# AFE.net
KiCad netlist of a schematic drawn in Altium Designer
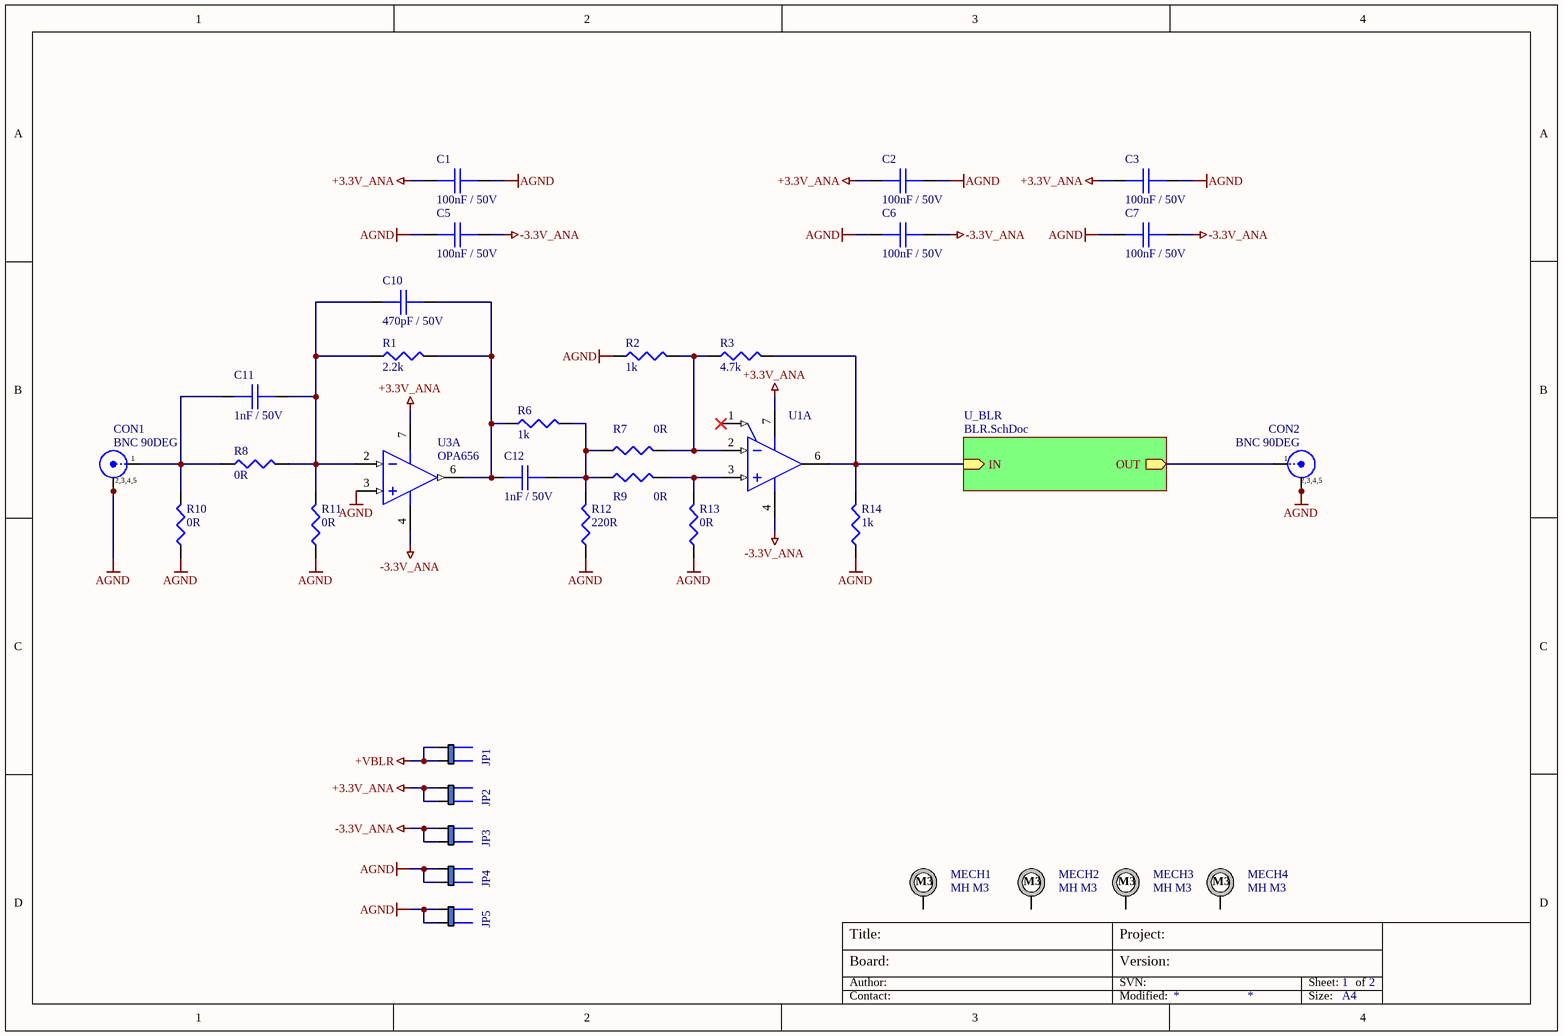
[diagram p0: AFE.SchDoc]

(export (version "E")
  (design (tool "Eeschema 10.0.6"))
  (components
    (comp (ref "C1")
      (value "100nF / 50V")
      (footprint "1206_C")
      (description "100nF 50V X7R")
      (fields (field (name "PART NUMBER") "SMD1206-100nF-50V"))
      (libsource (lib "ALTIUM_DB_LIB") (part "CAP_NONPOL"))
    )
    (comp (ref "C2")
      (value "100nF / 50V")
      (footprint "1206_C")
      (description "100nF 50V X7R")
      (fields (field (name "PART NUMBER") "SMD1206-100nF-50V"))
      (libsource (lib "ALTIUM_DB_LIB") (part "CAP_NONPOL"))
    )
    (comp (ref "C3")
      (value "100nF / 50V")
      (footprint "1206_C")
      (description "100nF 50V X7R")
      (fields (field (name "PART NUMBER") "SMD1206-100nF-50V"))
      (libsource (lib "ALTIUM_DB_LIB") (part "CAP_NONPOL"))
    )
    (comp (ref "C5")
      (value "100nF / 50V")
      (footprint "1206_C")
      (description "100nF 50V X7R")
      (fields (field (name "PART NUMBER") "SMD1206-100nF-50V"))
      (libsource (lib "ALTIUM_DB_LIB") (part "CAP_NONPOL"))
    )
    (comp (ref "C6")
      (value "100nF / 50V")
      (footprint "1206_C")
      (description "100nF 50V X7R")
      (fields (field (name "PART NUMBER") "SMD1206-100nF-50V"))
      (libsource (lib "ALTIUM_DB_LIB") (part "CAP_NONPOL"))
    )
    (comp (ref "C7")
      (value "100nF / 50V")
      (footprint "1206_C")
      (description "100nF 50V X7R")
      (fields (field (name "PART NUMBER") "SMD1206-100nF-50V"))
      (libsource (lib "ALTIUM_DB_LIB") (part "CAP_NONPOL"))
    )
    (comp (ref "C10")
      (value "470pF / 50V")
      (footprint "1206_C")
      (description "470pF 50V C0G")
      (fields (field (name "PART NUMBER") "SMD1206-470pF-50V"))
      (libsource (lib "ALTIUM_DB_LIB") (part "CAP_NONPOL"))
    )
    (comp (ref "C11")
      (value "1nF / 50V")
      (footprint "0805_C")
      (description "1nF 50V X7R")
      (fields (field (name "PART NUMBER") "SMD0805-1nF-50V"))
      (libsource (lib "ALTIUM_DB_LIB") (part "CAP_NONPOL"))
    )
    (comp (ref "C12")
      (value "1nF / 50V")
      (footprint "0603_C")
      (description "1 nF 50V X7R")
      (fields (field (name "PART NUMBER") "SMD0603-1nF-50V"))
      (libsource (lib "ALTIUM_DB_LIB") (part "CAP_NONPOL"))
    )
    (comp (ref "CON1")
      (value "BNC 90DEG")
      (footprint "CON_BNC_TE_ZDC")
      (description "031-5431")
      (libsource (lib "ALTIUM_DB_LIB") (part "CON_RF"))
    )
    (comp (ref "CON2")
      (value "BNC 90DEG")
      (footprint "CON_BNC_TE_ZDC")
      (description "031-5431")
      (libsource (lib "ALTIUM_DB_LIB") (part "CON_RF"))
    )
    (comp (ref "JP1")
      (value "JUMPER2 2.54MM")
      (footprint "JUMPER_5")
      (libsource (lib "ALTIUM_DB_LIB") (part "JUMPER2"))
    )
    (comp (ref "JP2")
      (value "JUMPER2 2.54MM")
      (footprint "JUMPER_5")
      (libsource (lib "ALTIUM_DB_LIB") (part "JUMPER2"))
    )
    (comp (ref "JP3")
      (value "JUMPER2 2.54MM")
      (footprint "JUMPER_5")
      (libsource (lib "ALTIUM_DB_LIB") (part "JUMPER2"))
    )
    (comp (ref "JP4")
      (value "JUMPER2 2.54MM")
      (footprint "JUMPER_5")
      (libsource (lib "ALTIUM_DB_LIB") (part "JUMPER2"))
    )
    (comp (ref "JP5")
      (value "JUMPER2 2.54MM")
      (footprint "JUMPER_5")
      (libsource (lib "ALTIUM_DB_LIB") (part "JUMPER2"))
    )
    (comp (ref "MECH1")
      (value "MH M3")
      (footprint "PAD_M3 x 7")
      (description "3.2/7mm Mounting_Hole_M3")
      (fields (field (name "PART NUMBER") "Mounting_Hole_M3"))
      (libsource (lib "ALTIUM_DB_LIB") (part "Mounting_Hole_M3"))
    )
    (comp (ref "MECH2")
      (value "MH M3")
      (footprint "PAD_M3 x 7")
      (description "3.2/7mm Mounting_Hole_M3")
      (fields (field (name "PART NUMBER") "Mounting_Hole_M3"))
      (libsource (lib "ALTIUM_DB_LIB") (part "Mounting_Hole_M3"))
    )
    (comp (ref "MECH3")
      (value "MH M3")
      (footprint "PAD_M3 x 7")
      (description "3.2/7mm Mounting_Hole_M3")
      (fields (field (name "PART NUMBER") "Mounting_Hole_M3"))
      (libsource (lib "ALTIUM_DB_LIB") (part "Mounting_Hole_M3"))
    )
    (comp (ref "MECH4")
      (value "MH M3")
      (footprint "PAD_M3 x 7")
      (description "3.2/7mm Mounting_Hole_M3")
      (fields (field (name "PART NUMBER") "Mounting_Hole_M3"))
      (libsource (lib "ALTIUM_DB_LIB") (part "Mounting_Hole_M3"))
    )
    (comp (ref "R1")
      (value "2.2k")
      (footprint "1206")
      (description "2.2k 1206 0.25W 5%")
      (fields (field (name "PART NUMBER") "SMD1206-2.2k 5%"))
      (libsource (lib "ALTIUM_DB_LIB") (part "RESISTOR"))
    )
    (comp (ref "R2")
      (value "1k")
      (footprint "1206")
      (description "1k 1206 0.25W 5%")
      (fields (field (name "PART NUMBER") "SMD1206-1k 5%"))
      (libsource (lib "ALTIUM_DB_LIB") (part "RESISTOR"))
    )
    (comp (ref "R3")
      (value "4.7k")
      (footprint "1206")
      (description "4.7k 1206 0.25W 5%")
      (fields (field (name "PART NUMBER") "SMD1206-4.7k 5%"))
      (libsource (lib "ALTIUM_DB_LIB") (part "RESISTOR"))
    )
    (comp (ref "R6")
      (value "1k")
      (footprint "1206")
      (description "1k 1206 0.25W 5%")
      (fields (field (name "PART NUMBER") "SMD1206-1k 5%"))
      (libsource (lib "ALTIUM_DB_LIB") (part "RESISTOR"))
    )
    (comp (ref "R7")
      (value "0R")
      (footprint "1206")
      (description "0R 1206 0.25W 5%")
      (fields (field (name "PART NUMBER") "SMD1206-0R 5%"))
      (libsource (lib "ALTIUM_DB_LIB") (part "RESISTOR"))
    )
    (comp (ref "R8")
      (value "0R")
      (footprint "1206")
      (description "0R 1206 0.25W 5%")
      (fields (field (name "PART NUMBER") "SMD1206-0R 5%"))
      (libsource (lib "ALTIUM_DB_LIB") (part "RESISTOR"))
    )
    (comp (ref "R9")
      (value "0R")
      (footprint "1206")
      (description "0R 1206 0.25W 5%")
      (fields (field (name "PART NUMBER") "SMD1206-0R 5%"))
      (libsource (lib "ALTIUM_DB_LIB") (part "RESISTOR"))
    )
    (comp (ref "R10")
      (value "0R")
      (footprint "1206")
      (description "0R 1206 0.25W 5%")
      (fields (field (name "PART NUMBER") "SMD1206-0R 5%"))
      (libsource (lib "ALTIUM_DB_LIB") (part "RESISTOR"))
    )
    (comp (ref "R11")
      (value "0R")
      (footprint "1206")
      (description "0R 1206 0.25W 5%")
      (fields (field (name "PART NUMBER") "SMD1206-0R 5%"))
      (libsource (lib "ALTIUM_DB_LIB") (part "RESISTOR"))
    )
    (comp (ref "R12")
      (value "220R")
      (footprint "0603")
      (description "220R 0603 0.1W 1%")
      (fields (field (name "PART NUMBER") "SMD0603-220R-1%"))
      (libsource (lib "ALTIUM_DB_LIB") (part "RESISTOR"))
    )
    (comp (ref "R13")
      (value "0R")
      (footprint "1206")
      (description "0R 1206 0.25W 5%")
      (fields (field (name "PART NUMBER") "SMD1206-0R 5%"))
      (libsource (lib "ALTIUM_DB_LIB") (part "RESISTOR"))
    )
    (comp (ref "R14")
      (value "1k")
      (footprint "1206")
      (description "1k 1206 0.25W 5%")
      (fields (field (name "PART NUMBER") "SMD1206-1k 5%"))
      (libsource (lib "ALTIUM_DB_LIB") (part "RESISTOR"))
    )
    (comp (ref "U1")
      (value "LT1806CS8#PBF")
      (footprint "SO-8")
      (fields
        (field (name "MANUFACTURER") "Linear Technology")
        (field (name "LINEAR TECHNOLOGY PART NUMBER") "LT1806")
      )
      (libsource (lib "ALTIUM_DB_LIB") (part "LT1806CS8#PBF"))
    )
    (comp (ref "U3")
      (value "OPA656")
      (footprint "SO-8")
      (fields (field (name "PARTNUMBER") "OPA656U") (field (name "MANUFACTURER") "Texas Instruments"))
      (libsource (lib "ALTIUM_DB_LIB") (part "OPA656"))
    )
  )
  (nets
    (net (code "1") (name "+3.3V_ANA") (class "Default")
      (node (ref "C1") (pin "1") (pintype "passive"))
      (node (ref "C2") (pin "1") (pintype "passive"))
      (node (ref "C3") (pin "1") (pintype "passive"))
      (node (ref "JP2") (pin "1") (pinfunction "1_1") (pintype "passive"))
      (node (ref "JP2") (pin "2") (pinfunction "2_2") (pintype "passive"))
      (node (ref "U1") (pin "7") (pinfunction "V+_7") (pintype "power_in"))
      (node (ref "U3") (pin "7") (pinfunction "VS+_7") (pintype "power_in"))
    )
    (net (code "2") (name "+VBLR") (class "Default")
      (node (ref "JP1") (pin "1") (pinfunction "1_1") (pintype "passive"))
      (node (ref "JP1") (pin "2") (pinfunction "2_2") (pintype "passive"))
    )
    (net (code "3") (name "-3.3V_ANA") (class "Default")
      (node (ref "C5") (pin "2") (pintype "passive"))
      (node (ref "C6") (pin "2") (pintype "passive"))
      (node (ref "C7") (pin "2") (pintype "passive"))
      (node (ref "JP3") (pin "1") (pinfunction "1_1") (pintype "passive"))
      (node (ref "JP3") (pin "2") (pinfunction "2_2") (pintype "passive"))
      (node (ref "U1") (pin "4") (pinfunction "V-_4") (pintype "power_in"))
      (node (ref "U3") (pin "4") (pinfunction "VS-_4") (pintype "power_in"))
    )
    (net (code "4") (name "/IN") (class "Default")
      (node (ref "R14") (pin "2") (pintype "passive"))
      (node (ref "R3") (pin "2") (pintype "passive"))
      (node (ref "U1") (pin "6") (pinfunction "OUT_6") (pintype "tri_state"))
    )
    (net (code "5") (name "/OUT") (class "Default")
      (node (ref "CON2") (pin "1") (pinfunction "1_1") (pintype "passive"))
    )
    (net (code "6") (name "AGND") (class "Default")
      (node (ref "C1") (pin "2") (pintype "passive"))
      (node (ref "C2") (pin "2") (pintype "passive"))
      (node (ref "C3") (pin "2") (pintype "passive"))
      (node (ref "C5") (pin "1") (pintype "passive"))
      (node (ref "C6") (pin "1") (pintype "passive"))
      (node (ref "C7") (pin "1") (pintype "passive"))
      (node (ref "CON1") (pin "2") (pinfunction "2_2") (pintype "passive"))
      (node (ref "CON1") (pin "3") (pinfunction "3_3") (pintype "passive"))
      (node (ref "CON1") (pin "4") (pinfunction "4_4") (pintype "passive"))
      (node (ref "CON1") (pin "5") (pinfunction "5_5") (pintype "passive"))
      (node (ref "CON2") (pin "2") (pinfunction "2_2") (pintype "passive"))
      (node (ref "CON2") (pin "3") (pinfunction "3_3") (pintype "passive"))
      (node (ref "CON2") (pin "4") (pinfunction "4_4") (pintype "passive"))
      (node (ref "CON2") (pin "5") (pinfunction "5_5") (pintype "passive"))
      (node (ref "JP4") (pin "1") (pinfunction "1_1") (pintype "passive"))
      (node (ref "JP4") (pin "2") (pinfunction "2_2") (pintype "passive"))
      (node (ref "JP5") (pin "1") (pinfunction "1_1") (pintype "passive"))
      (node (ref "JP5") (pin "2") (pinfunction "2_2") (pintype "passive"))
      (node (ref "R10") (pin "1") (pintype "passive"))
      (node (ref "R11") (pin "1") (pintype "passive"))
      (node (ref "R12") (pin "1") (pintype "passive"))
      (node (ref "R13") (pin "1") (pintype "passive"))
      (node (ref "R14") (pin "1") (pintype "passive"))
      (node (ref "R2") (pin "1") (pintype "passive"))
      (node (ref "U3") (pin "3") (pinfunction "IN+_3") (pintype "input"))
    )
    (net (code "7") (name "Net-(C11-Pad1)") (class "Default")
      (node (ref "C11") (pin "1") (pintype "passive"))
      (node (ref "CON1") (pin "1") (pinfunction "1_1") (pintype "passive"))
      (node (ref "R10") (pin "2") (pintype "passive"))
      (node (ref "R8") (pin "1") (pintype "passive"))
    )
    (net (code "8") (name "Net-(C12-Pad2)") (class "Default")
      (node (ref "C12") (pin "2") (pintype "passive"))
      (node (ref "R12") (pin "2") (pintype "passive"))
      (node (ref "R6") (pin "2") (pintype "passive"))
      (node (ref "R7") (pin "1") (pintype "passive"))
      (node (ref "R9") (pin "1") (pintype "passive"))
    )
    (net (code "9") (name "Net-(U1A-+IN)") (class "Default")
      (node (ref "R13") (pin "2") (pintype "passive"))
      (node (ref "R9") (pin "2") (pintype "passive"))
      (node (ref "U1") (pin "3") (pinfunction "+IN_3") (pintype "input"))
    )
    (net (code "10") (name "Net-(U1A--IN)") (class "Default")
      (node (ref "R2") (pin "2") (pintype "passive"))
      (node (ref "R3") (pin "1") (pintype "passive"))
      (node (ref "R7") (pin "2") (pintype "passive"))
      (node (ref "U1") (pin "2") (pinfunction "-IN_2") (pintype "input"))
    )
    (net (code "11") (name "Net-(U3A-IN-)") (class "Default")
      (node (ref "C10") (pin "2") (pintype "passive"))
      (node (ref "C11") (pin "2") (pintype "passive"))
      (node (ref "R1") (pin "2") (pintype "passive"))
      (node (ref "R11") (pin "2") (pintype "passive"))
      (node (ref "R8") (pin "2") (pintype "passive"))
      (node (ref "U3") (pin "2") (pinfunction "IN-_2") (pintype "input"))
    )
    (net (code "12") (name "Net-(U3A-OUT)") (class "Default")
      (node (ref "C10") (pin "1") (pintype "passive"))
      (node (ref "C12") (pin "1") (pintype "passive"))
      (node (ref "R1") (pin "1") (pintype "passive"))
      (node (ref "R6") (pin "1") (pintype "passive"))
      (node (ref "U3") (pin "6") (pinfunction "OUT_6") (pintype "output"))
    )
    (net (code "13") (name "unconnected-(MECH1-PadM3)") (class "Default")
      (node (ref "MECH1") (pin "M3") (pinfunction "M3_M3") (pintype "passive"))
    )
    (net (code "14") (name "unconnected-(MECH2-PadM3)") (class "Default")
      (node (ref "MECH2") (pin "M3") (pinfunction "M3_M3") (pintype "passive"))
    )
    (net (code "15") (name "unconnected-(MECH3-PadM3)") (class "Default")
      (node (ref "MECH3") (pin "M3") (pinfunction "M3_M3") (pintype "passive"))
    )
    (net (code "16") (name "unconnected-(MECH4-PadM3)") (class "Default")
      (node (ref "MECH4") (pin "M3") (pinfunction "M3_M3") (pintype "passive"))
    )
    (net (code "17") (name "unconnected-(U1A-~{SHDN}-Pad1)") (class "Default")
      (node (ref "U1") (pin "1") (pinfunction "~{SHDN}_1") (pintype "input+no_connect"))
    )
  )
)
